# SensorConfiguration.net
KiCad netlist of a schematic drawn in EAGLE
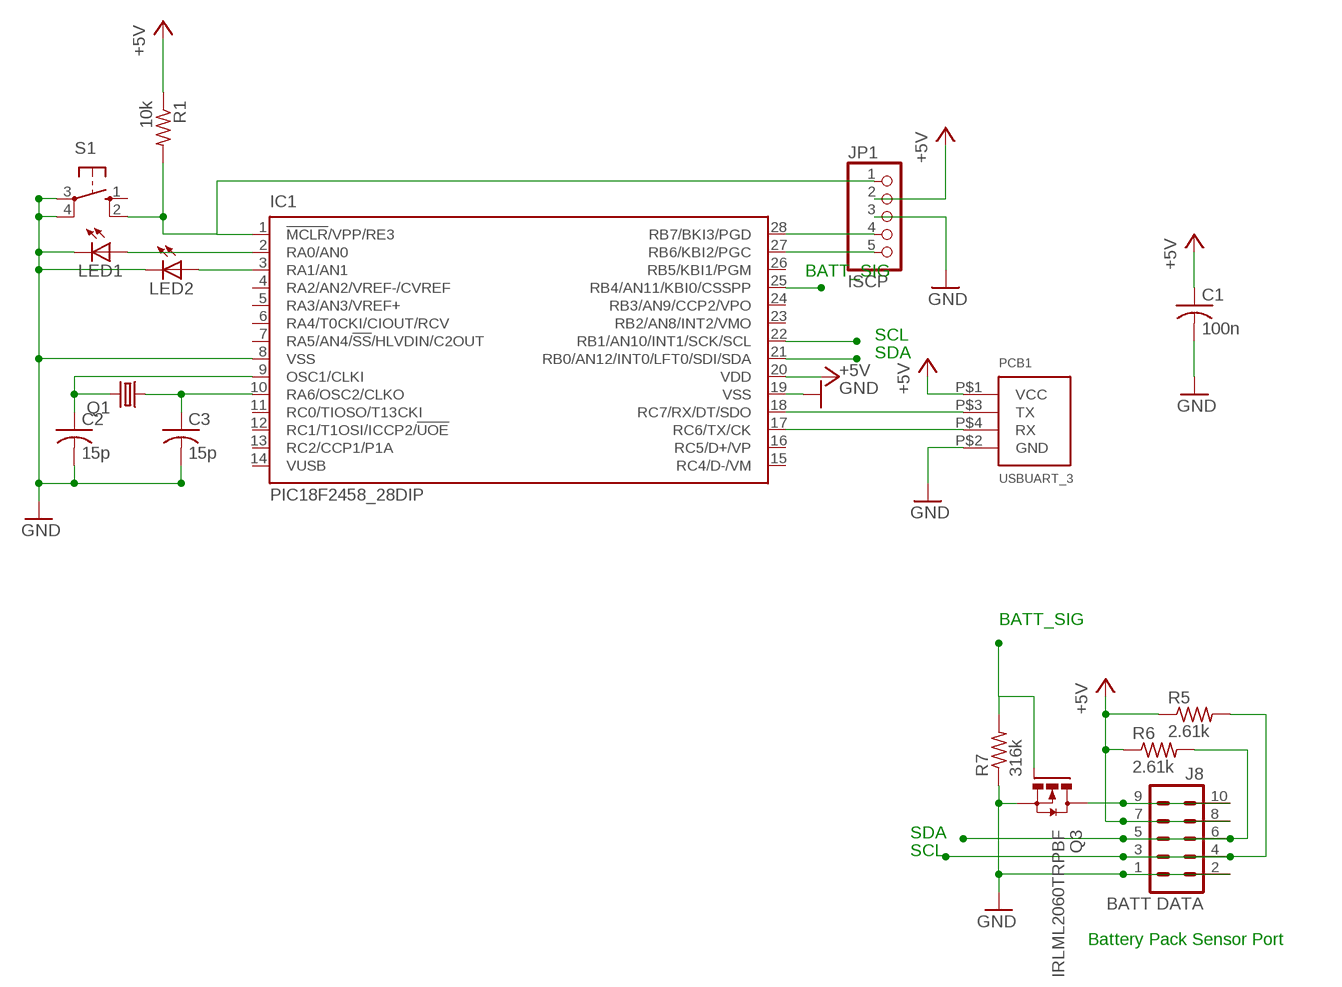
[diagram p0: schematic, sheet 1]

(export (version "E")
  (design (tool "Eeschema 10.0.6"))
  (components
    (comp (ref "C1")
      (value "100n")
      (footprint "eagle-import:C0805")
      (libsource (lib "eagle-import") (part "C-USC0805"))
    )
    (comp (ref "C2")
      (value "15p")
      (footprint "eagle-import:C0805")
      (libsource (lib "eagle-import") (part "C-USC0805"))
    )
    (comp (ref "C3")
      (value "15p")
      (footprint "eagle-import:C0805")
      (libsource (lib "eagle-import") (part "C-USC0805"))
    )
    (comp (ref "IC1")
      (value "PIC18F2458_28DIP")
      (footprint "eagle-import:DIL28-3")
      (fields (field (name "MF") "MICROCHIP") (field (name "MPN") "PIC18F2455-I/SP"))
      (libsource (lib "eagle-import") (part "PIC18F2_28DIP455"))
    )
    (comp (ref "J8")
      (value "BATT DATA")
      (footprint "eagle-import:ML10")
      (libsource (lib "eagle-import") (part "ML10"))
    )
    (comp (ref "JP1")
      (value "ISCP")
      (footprint "eagle-import:1X05")
      (libsource (lib "eagle-import") (part "PINHD-1X5"))
    )
    (comp (ref "LED1")
      (value "LED5MM")
      (footprint "eagle-import:LED5MM")
      (libsource (lib "eagle-import") (part "LED5MM"))
    )
    (comp (ref "LED2")
      (value "LED5MM")
      (footprint "eagle-import:LED5MM")
      (libsource (lib "eagle-import") (part "LED5MM"))
    )
    (comp (ref "PCB1")
      (value "USBUART_3")
      (footprint "eagle-import:UB232R")
      (libsource (lib "eagle-import") (part "USBUART_3"))
    )
    (comp (ref "Q1")
      (value "CRYSTALHC49S")
      (footprint "eagle-import:HC49_S")
      (libsource (lib "eagle-import") (part "CRYSTALHC49S"))
    )
    (comp (ref "Q3")
      (value "IRLML2060TRPBF")
      (footprint "eagle-import:SOT23")
      (libsource (lib "eagle-import") (part "IRLML2060TRPBF"))
    )
    (comp (ref "R1")
      (value "10k")
      (footprint "eagle-import:R0805")
      (libsource (lib "eagle-import") (part "resistor_R-US_R0805"))
    )
    (comp (ref "R5")
      (value "2.61k")
      (footprint "eagle-import:R0805")
      (libsource (lib "eagle-import") (part "R-US_R0805"))
    )
    (comp (ref "R6")
      (value "2.61k")
      (footprint "eagle-import:R0805")
      (libsource (lib "eagle-import") (part "R-US_R0805"))
    )
    (comp (ref "R7")
      (value "316k")
      (footprint "eagle-import:R0805")
      (libsource (lib "eagle-import") (part "R-US_R0805"))
    )
    (comp (ref "S1")
      (value "10-XX")
      (footprint "eagle-import:B3F-10XX")
      (fields (field (name "MPN") "B3F-1000"))
      (libsource (lib "eagle-import") (part "10-XX"))
    )
  )
  (nets
    (net (code "1") (name "+5V") (class "Default")
      (node (ref "C1") (pin "1") (pinfunction "1_1") (pintype "passive"))
      (node (ref "IC1") (pin "20") (pinfunction "VDD_20") (pintype "power_in"))
      (node (ref "J8") (pin "7") (pinfunction "7_7") (pintype "passive"))
      (node (ref "J8") (pin "8") (pinfunction "8_8") (pintype "passive"))
      (node (ref "JP1") (pin "2") (pinfunction "2_2") (pintype "passive"))
      (node (ref "PCB1") (pin "P$1") (pinfunction "VCC_P$1") (pintype "power_in"))
      (node (ref "R1") (pin "1") (pinfunction "1_1") (pintype "passive"))
      (node (ref "R5") (pin "1") (pinfunction "1_1") (pintype "passive"))
      (node (ref "R6") (pin "1") (pinfunction "1_1") (pintype "passive"))
    )
    (net (code "2") (name "/BSIG") (class "Default")
      (node (ref "IC1") (pin "25") (pinfunction "RB4/AN11/KBI0/CSSPP_25") (pintype "bidirectional"))
      (node (ref "Q3") (pin "1") (pinfunction "G_1") (pintype "passive"))
      (node (ref "R7") (pin "2") (pinfunction "2_2") (pintype "passive"))
    )
    (net (code "3") (name "/SCL") (class "Default")
      (node (ref "IC1") (pin "22") (pinfunction "RB1/AN10/INT1/SCK/SCL_22") (pintype "bidirectional"))
      (node (ref "J8") (pin "3") (pinfunction "3_3") (pintype "passive"))
      (node (ref "J8") (pin "4") (pinfunction "4_4") (pintype "passive"))
      (node (ref "R5") (pin "2") (pinfunction "2_2") (pintype "passive"))
    )
    (net (code "4") (name "/SDA") (class "Default")
      (node (ref "IC1") (pin "21") (pinfunction "RB0/AN12/INT0/LFT0/SDI/SDA_21") (pintype "bidirectional"))
      (node (ref "J8") (pin "5") (pinfunction "5_5") (pintype "passive"))
      (node (ref "J8") (pin "6") (pinfunction "6_6") (pintype "passive"))
      (node (ref "R6") (pin "2") (pinfunction "2_2") (pintype "passive"))
    )
    (net (code "5") (name "GND") (class "Default")
      (node (ref "C1") (pin "2") (pinfunction "2_2") (pintype "passive"))
      (node (ref "C2") (pin "2") (pinfunction "2_2") (pintype "passive"))
      (node (ref "C3") (pin "2") (pinfunction "2_2") (pintype "passive"))
      (node (ref "IC1") (pin "19") (pinfunction "VSS_19") (pintype "power_in"))
      (node (ref "IC1") (pin "8") (pinfunction "VSS_8") (pintype "power_in"))
      (node (ref "J8") (pin "1") (pinfunction "1_1") (pintype "passive"))
      (node (ref "J8") (pin "2") (pinfunction "2_2") (pintype "passive"))
      (node (ref "JP1") (pin "3") (pinfunction "3_3") (pintype "passive"))
      (node (ref "LED1") (pin "K") (pinfunction "C_K") (pintype "passive"))
      (node (ref "LED2") (pin "K") (pinfunction "C_K") (pintype "passive"))
      (node (ref "PCB1") (pin "P$2") (pinfunction "GND_P$2") (pintype "power_in"))
      (node (ref "Q3") (pin "2") (pinfunction "S_2") (pintype "passive"))
      (node (ref "R7") (pin "1") (pinfunction "1_1") (pintype "passive"))
      (node (ref "S1") (pin "3") (pinfunction "P_3") (pintype "passive"))
      (node (ref "S1") (pin "4") (pinfunction "P1_4") (pintype "passive"))
    )
    (net (code "6") (name "Net-(IC1-OSC1{slash}CLKI)") (class "Default")
      (node (ref "C2") (pin "1") (pinfunction "1_1") (pintype "passive"))
      (node (ref "IC1") (pin "9") (pinfunction "OSC1/CLKI_9") (pintype "input"))
      (node (ref "Q1") (pin "2") (pinfunction "2_2") (pintype "passive"))
    )
    (net (code "7") (name "Net-(IC1-RA0{slash}AN0)") (class "Default")
      (node (ref "IC1") (pin "2") (pinfunction "RA0/AN0_2") (pintype "bidirectional"))
      (node (ref "LED1") (pin "A") (pinfunction "A_A") (pintype "passive"))
    )
    (net (code "8") (name "Net-(IC1-RA1{slash}AN1)") (class "Default")
      (node (ref "IC1") (pin "3") (pinfunction "RA1/AN1_3") (pintype "bidirectional"))
      (node (ref "LED2") (pin "A") (pinfunction "A_A") (pintype "passive"))
    )
    (net (code "9") (name "Net-(IC1-RA6{slash}OSC2{slash}CLKO)") (class "Default")
      (node (ref "C3") (pin "1") (pinfunction "1_1") (pintype "passive"))
      (node (ref "IC1") (pin "10") (pinfunction "RA6/OSC2/CLKO_10") (pintype "output"))
      (node (ref "Q1") (pin "1") (pinfunction "1_1") (pintype "passive"))
    )
    (net (code "10") (name "Net-(IC1-RB6{slash}KBI2{slash}PGC)") (class "Default")
      (node (ref "IC1") (pin "27") (pinfunction "RB6/KBI2/PGC_27") (pintype "bidirectional"))
      (node (ref "JP1") (pin "5") (pinfunction "5_5") (pintype "passive"))
    )
    (net (code "11") (name "Net-(IC1-RB7{slash}BKI3{slash}PGD)") (class "Default")
      (node (ref "IC1") (pin "28") (pinfunction "RB7/BKI3/PGD_28") (pintype "bidirectional"))
      (node (ref "JP1") (pin "4") (pinfunction "4_4") (pintype "passive"))
    )
    (net (code "12") (name "Net-(IC1-RC6{slash}TX{slash}CK)") (class "Default")
      (node (ref "IC1") (pin "17") (pinfunction "RC6/TX/CK_17") (pintype "bidirectional"))
      (node (ref "PCB1") (pin "P$4") (pinfunction "RX_P$4") (pintype "input"))
    )
    (net (code "13") (name "Net-(IC1-RC7{slash}RX{slash}DT{slash}SDO)") (class "Default")
      (node (ref "IC1") (pin "18") (pinfunction "RC7/RX/DT/SDO_18") (pintype "bidirectional"))
      (node (ref "PCB1") (pin "P$3") (pinfunction "TX_P$3") (pintype "output"))
    )
    (net (code "14") (name "Net-(IC1-~{MCLR}{slash}VPP{slash}RE3)") (class "Default")
      (node (ref "IC1") (pin "1") (pinfunction "~{MCLR}/VPP/RE3_1") (pintype "input"))
      (node (ref "JP1") (pin "1") (pinfunction "1_1") (pintype "passive"))
      (node (ref "R1") (pin "2") (pinfunction "2_2") (pintype "passive"))
      (node (ref "S1") (pin "2") (pinfunction "S1_2") (pintype "passive"))
    )
    (net (code "15") (name "Net-(Q3-D)") (class "Default")
      (node (ref "J8") (pin "10") (pinfunction "10_10") (pintype "passive"))
      (node (ref "J8") (pin "9") (pinfunction "9_9") (pintype "passive"))
      (node (ref "Q3") (pin "3") (pinfunction "D_3") (pintype "passive"))
    )
    (net (code "16") (name "unconnected-(IC1-RA2{slash}AN2{slash}VREF-{slash}CVREF-Pad4)") (class "Default")
      (node (ref "IC1") (pin "4") (pinfunction "RA2/AN2/VREF-/CVREF_4") (pintype "bidirectional"))
    )
    (net (code "17") (name "unconnected-(IC1-RA3{slash}AN3{slash}VREF+-Pad5)") (class "Default")
      (node (ref "IC1") (pin "5") (pinfunction "RA3/AN3/VREF+_5") (pintype "bidirectional"))
    )
    (net (code "18") (name "unconnected-(IC1-RA4{slash}T0CKI{slash}CIOUT{slash}RCV-Pad6)") (class "Default")
      (node (ref "IC1") (pin "6") (pinfunction "RA4/T0CKI/CIOUT/RCV_6") (pintype "bidirectional"))
    )
    (net (code "19") (name "unconnected-(IC1-RA5{slash}AN4{slash}~{SS}{slash}HLVDIN{slash}C2OUT-Pad7)") (class "Default")
      (node (ref "IC1") (pin "7") (pinfunction "RA5/AN4/~{SS}/HLVDIN/C2OUT_7") (pintype "bidirectional"))
    )
    (net (code "20") (name "unconnected-(IC1-RB2{slash}AN8{slash}INT2{slash}VMO-Pad23)") (class "Default")
      (node (ref "IC1") (pin "23") (pinfunction "RB2/AN8/INT2/VMO_23") (pintype "bidirectional"))
    )
    (net (code "21") (name "unconnected-(IC1-RB3{slash}AN9{slash}CCP2{slash}VPO-Pad24)") (class "Default")
      (node (ref "IC1") (pin "24") (pinfunction "RB3/AN9/CCP2/VPO_24") (pintype "bidirectional"))
    )
    (net (code "22") (name "unconnected-(IC1-RB5{slash}KBI1{slash}PGM-Pad26)") (class "Default")
      (node (ref "IC1") (pin "26") (pinfunction "RB5/KBI1/PGM_26") (pintype "bidirectional"))
    )
    (net (code "23") (name "unconnected-(IC1-RC0{slash}TIOSO{slash}T13CKI-Pad11)") (class "Default")
      (node (ref "IC1") (pin "11") (pinfunction "RC0/TIOSO/T13CKI_11") (pintype "bidirectional"))
    )
    (net (code "24") (name "unconnected-(IC1-RC1{slash}T1OSI{slash}ICCP2{slash}~{UOE}-Pad12)") (class "Default")
      (node (ref "IC1") (pin "12") (pinfunction "RC1/T1OSI/ICCP2/~{UOE}_12") (pintype "bidirectional"))
    )
    (net (code "25") (name "unconnected-(IC1-RC2{slash}CCP1{slash}P1A-Pad13)") (class "Default")
      (node (ref "IC1") (pin "13") (pinfunction "RC2/CCP1/P1A_13") (pintype "bidirectional"))
    )
    (net (code "26") (name "unconnected-(IC1-RC4{slash}D-{slash}VM-Pad15)") (class "Default")
      (node (ref "IC1") (pin "15") (pinfunction "RC4/D-/VM_15") (pintype "bidirectional"))
    )
    (net (code "27") (name "unconnected-(IC1-RC5{slash}D+{slash}VP-Pad16)") (class "Default")
      (node (ref "IC1") (pin "16") (pinfunction "RC5/D+/VP_16") (pintype "bidirectional"))
    )
    (net (code "28") (name "unconnected-(IC1-VUSB-Pad14)") (class "Default")
      (node (ref "IC1") (pin "14") (pinfunction "VUSB_14") (pintype "bidirectional"))
    )
    (net (code "29") (name "unconnected-(S1-S-Pad1)") (class "Default")
      (node (ref "S1") (pin "1") (pinfunction "S_1") (pintype "passive"))
    )
  )
)
